# Tray2_Comms_DTMF.net
KiCad netlist of a schematic drawn in Altium Designer
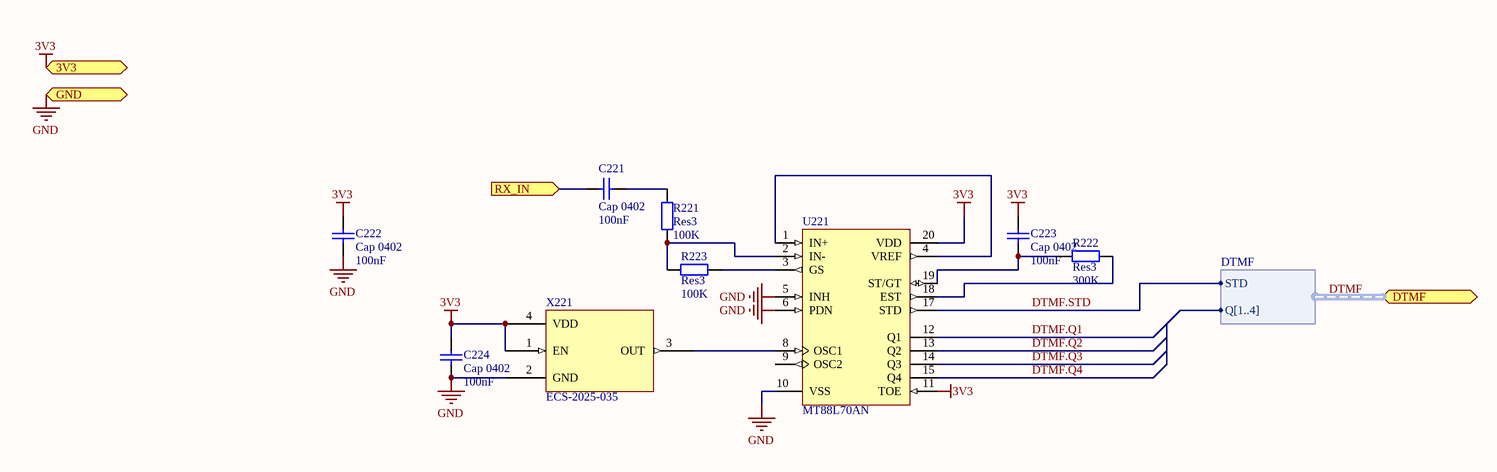
[diagram p0: Tray2_Comms_DTMF.SchDoc]

(export (version "E")
  (design (tool "Eeschema 10.0.6"))
  (components
    (comp (ref "C221")
      (value "Cap 0402")
      (footprint "CAPC1005X06L")
      (description "Capacitor")
      (fields (field (name "ALTIUM_VALUE") "100nF") (field (name "PUBLISHER") "Altium Limited"))
      (libsource (lib "CSC") (part "Cap 0402"))
    )
    (comp (ref "C222")
      (value "Cap 0402")
      (footprint "CAPC1005X06L")
      (description "Capacitor")
      (fields (field (name "ALTIUM_VALUE") "100nF") (field (name "PUBLISHER") "Altium Limited"))
      (libsource (lib "CSC") (part "Cap 0402"))
    )
    (comp (ref "C223")
      (value "Cap 0402")
      (footprint "CAPC1005X06L")
      (description "Capacitor")
      (fields (field (name "ALTIUM_VALUE") "100nF") (field (name "PUBLISHER") "Altium Limited"))
      (libsource (lib "CSC") (part "Cap 0402"))
    )
    (comp (ref "C224")
      (value "Cap 0402")
      (footprint "CAPC1005X06L")
      (description "Capacitor")
      (fields (field (name "ALTIUM_VALUE") "100nF") (field (name "PUBLISHER") "Altium Limited"))
      (libsource (lib "CSC") (part "Cap 0402"))
    )
    (comp (ref "R221")
      (value "Res3")
      (footprint "RESC1005X06L")
      (description "Resistor")
      (fields (field (name "ALTIUM_VALUE") "100K") (field (name "PUBLISHER") "Altium Limited"))
      (libsource (lib "CSC") (part "Res3"))
    )
    (comp (ref "R222")
      (value "Res3")
      (footprint "RESC1005X06L")
      (description "Resistor")
      (fields (field (name "ALTIUM_VALUE") "300K") (field (name "PUBLISHER") "Altium Limited"))
      (libsource (lib "") (part "Res3_1"))
    )
    (comp (ref "R223")
      (value "Res3")
      (footprint "RESC1005X06L")
      (description "Resistor")
      (fields (field (name "ALTIUM_VALUE") "100K") (field (name "PUBLISHER") "Altium Limited"))
      (libsource (lib "") (part "Res3_1"))
    )
    (comp (ref "U221")
      (value "MT88L70AN")
      (footprint "TSSOP20")
      (description "3 Volt Integrated DTMF Receiver")
      (fields (field (name "PUBLISHER") "Altium Limited"))
      (libsource (lib "Comms Board Small Footprints") (part "MT88L70AN"))
    )
    (comp (ref "X221")
      (value "ECS-2025-035")
      (footprint "ECS-2025")
      (description "SMD Clock Oscillator, 3.579545MHz")
      (libsource (lib "Comms Board Small Footprints") (part "ECS-2025-035"))
    )
  )
  (nets
    (net (code "2") (name "/DTMF.Q1") (class "Default")
      (node (ref "U221") (pin "12") (pinfunction "Q1_12") (pintype "tri_state"))
    )
    (net (code "3") (name "/DTMF.Q2") (class "Default")
      (node (ref "U221") (pin "13") (pinfunction "Q2_13") (pintype "tri_state"))
    )
    (net (code "4") (name "/DTMF.Q3") (class "Default")
      (node (ref "U221") (pin "14") (pinfunction "Q3_14") (pintype "tri_state"))
    )
    (net (code "5") (name "/DTMF.Q4") (class "Default")
      (node (ref "U221") (pin "15") (pinfunction "Q4_15") (pintype "tri_state"))
    )
    (net (code "6") (name "/DTMF.STD") (class "Default")
      (node (ref "U221") (pin "17") (pinfunction "STD_17") (pintype "output"))
    )
    (net (code "8") (name "/RX_IN") (class "Default")
      (node (ref "C221") (pin "2") (pinfunction "2_2") (pintype "passive"))
    )
    (net (code "9") (name "3V3") (class "Default")
      (node (ref "C222") (pin "2") (pinfunction "2_2") (pintype "passive"))
      (node (ref "C223") (pin "1") (pinfunction "1_1") (pintype "passive"))
      (node (ref "C224") (pin "1") (pinfunction "1_1") (pintype "passive"))
      (node (ref "U221") (pin "11") (pinfunction "TOE_11") (pintype "input"))
      (node (ref "U221") (pin "20") (pinfunction "VDD_20") (pintype "power_in"))
      (node (ref "X221") (pin "1") (pinfunction "EN_1") (pintype "input"))
      (node (ref "X221") (pin "4") (pinfunction "VDD_4") (pintype "power_in"))
    )
    (net (code "10") (name "GND") (class "Default")
      (node (ref "C222") (pin "1") (pinfunction "1_1") (pintype "passive"))
      (node (ref "C224") (pin "2") (pinfunction "2_2") (pintype "passive"))
      (node (ref "U221") (pin "10") (pinfunction "VSS_10") (pintype "power_in"))
      (node (ref "U221") (pin "5") (pinfunction "INH_5") (pintype "input"))
      (node (ref "U221") (pin "6") (pinfunction "PDN_6") (pintype "input"))
      (node (ref "X221") (pin "2") (pinfunction "GND_2") (pintype "power_in"))
    )
    (net (code "11") (name "Net-(C221-Pad1)") (class "Default")
      (node (ref "C221") (pin "1") (pinfunction "1_1") (pintype "passive"))
      (node (ref "R221") (pin "1") (pinfunction "1_1") (pintype "passive"))
    )
    (net (code "12") (name "Net-(U221-EST)") (class "Default")
      (node (ref "R222") (pin "2") (pinfunction "2_2") (pintype "passive"))
      (node (ref "U221") (pin "18") (pinfunction "EST_18") (pintype "output"))
    )
    (net (code "13") (name "Net-(U221-GS)") (class "Default")
      (node (ref "R223") (pin "2") (pinfunction "2_2") (pintype "passive"))
      (node (ref "U221") (pin "3") (pinfunction "GS_3") (pintype "output"))
    )
    (net (code "14") (name "Net-(U221-IN+)") (class "Default")
      (node (ref "U221") (pin "1") (pinfunction "IN+_1") (pintype "input"))
      (node (ref "U221") (pin "4") (pinfunction "VREF_4") (pintype "output"))
    )
    (net (code "15") (name "Net-(U221-IN-)") (class "Default")
      (node (ref "R221") (pin "2") (pinfunction "2_2") (pintype "passive"))
      (node (ref "R223") (pin "1") (pinfunction "1_1") (pintype "passive"))
      (node (ref "U221") (pin "2") (pinfunction "IN-_2") (pintype "input"))
    )
    (net (code "16") (name "Net-(U221-OSC1)") (class "Default")
      (node (ref "U221") (pin "8") (pinfunction "OSC1_8") (pintype "input"))
      (node (ref "X221") (pin "3") (pinfunction "OUT_3") (pintype "output"))
    )
    (net (code "17") (name "Net-(U221-ST{slash}GT)") (class "Default")
      (node (ref "C223") (pin "2") (pinfunction "2_2") (pintype "passive"))
      (node (ref "R222") (pin "1") (pinfunction "1_1") (pintype "passive"))
      (node (ref "U221") (pin "19") (pinfunction "ST/GT_19") (pintype "bidirectional"))
    )
    (net (code "18") (name "unconnected-(U221-OSC2-Pad9)") (class "Default")
      (node (ref "U221") (pin "9") (pinfunction "OSC2_9") (pintype "output"))
    )
  )
)
